# basic_schematic_pullup.net
KiCad netlist of a schematic drawn in EAGLE
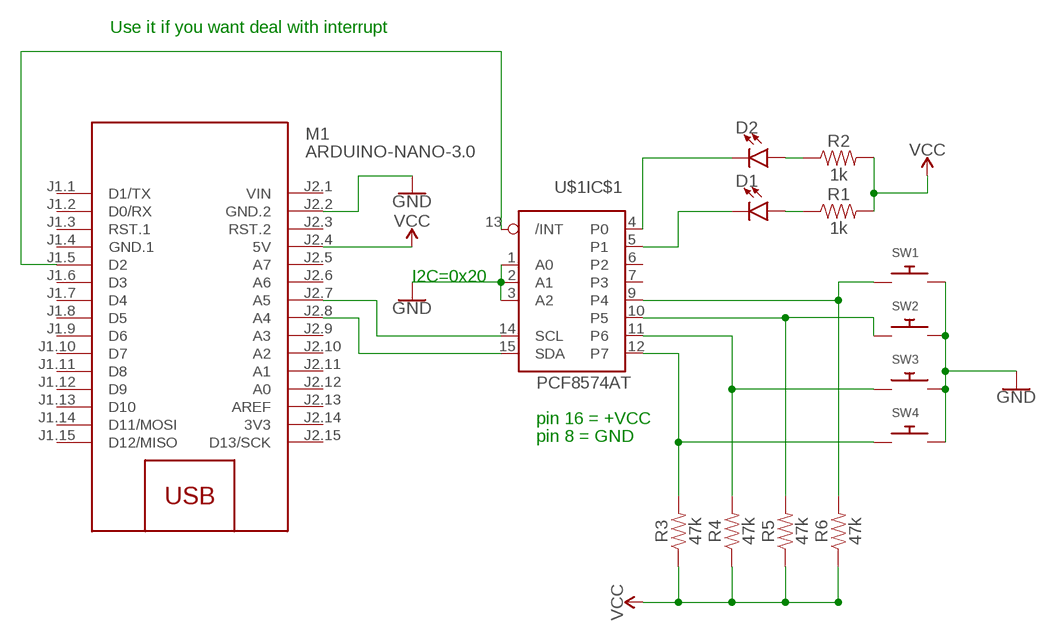
[diagram p0: schematic, sheet 1]

(export (version "E")
  (design (tool "Eeschema 10.0.6"))
  (components
    (comp (ref "D1")
      (value "LED3MM")
      (footprint "eagle-import:LED_3MM")
      (libsource (lib "eagle-import") (part "LED3MM"))
    )
    (comp (ref "D2")
      (value "LED3MM")
      (footprint "eagle-import:LED_3MM")
      (libsource (lib "eagle-import") (part "LED3MM"))
    )
    (comp (ref "M1")
      (value "ARDUINO-NANO-3.0")
      (footprint "eagle-import:ARDUINO-NANO-3.0")
      (libsource (lib "eagle-import") (part "ARDUINO-NANO-3.0"))
    )
    (comp (ref "R1")
      (value "1k")
      (footprint "eagle-import:0603")
      (libsource (lib "eagle-import") (part "1KOHM-0603-1/10W-1%"))
    )
    (comp (ref "R2")
      (value "1k")
      (footprint "eagle-import:0603")
      (libsource (lib "eagle-import") (part "1KOHM-0603-1/10W-1%"))
    )
    (comp (ref "R3")
      (value "47k")
      (footprint "eagle-import:0603")
      (libsource (lib "eagle-import") (part "47KOHM-0603-1/10W-1%"))
    )
    (comp (ref "R4")
      (value "47k")
      (footprint "eagle-import:0603")
      (libsource (lib "eagle-import") (part "47KOHM-0603-1/10W-1%"))
    )
    (comp (ref "R5")
      (value "47k")
      (footprint "eagle-import:0603")
      (libsource (lib "eagle-import") (part "47KOHM-0603-1/10W-1%"))
    )
    (comp (ref "R6")
      (value "47k")
      (footprint "eagle-import:0603")
      (libsource (lib "eagle-import") (part "47KOHM-0603-1/10W-1%"))
    )
    (comp (ref "SW1")
      (value "SWITCH_PUSHBUTTONC&K_KSS")
      (footprint "eagle-import:BTN_CK_KSS")
      (libsource (lib "eagle-import") (part "SWITCH_PUSHBUTTONC&K_KSS"))
    )
    (comp (ref "SW2")
      (value "SWITCH_PUSHBUTTONC&K_KSS")
      (footprint "eagle-import:BTN_CK_KSS")
      (libsource (lib "eagle-import") (part "SWITCH_PUSHBUTTONC&K_KSS"))
    )
    (comp (ref "SW3")
      (value "SWITCH_PUSHBUTTONC&K_KSS")
      (footprint "eagle-import:BTN_CK_KSS")
      (libsource (lib "eagle-import") (part "SWITCH_PUSHBUTTONC&K_KSS"))
    )
    (comp (ref "SW4")
      (value "SWITCH_PUSHBUTTONC&K_KSS")
      (footprint "eagle-import:BTN_CK_KSS")
      (libsource (lib "eagle-import") (part "SWITCH_PUSHBUTTONC&K_KSS"))
    )
    (comp (ref "U$1")
      (value "PCF8574AT")
      (footprint "eagle-import:SO16")
      (libsource (lib "eagle-import") (part "PCF8574AT"))
    )
  )
  (nets
    (net (code "1") (name "/3V3") (class "Default")
      (node (ref "M1") (pin "J2.14") (pinfunction "3V3_J2.14") (pintype "power_in"))
    )
    (net (code "2") (name "/GND.1") (class "Default")
      (node (ref "M1") (pin "J1.4") (pinfunction "GND.1_J1.4") (pintype "power_in"))
    )
    (net (code "3") (name "/VIN") (class "Default")
      (node (ref "M1") (pin "J2.1") (pinfunction "VIN_J2.1") (pintype "power_in"))
    )
    (net (code "4") (name "GND") (class "Default")
      (node (ref "M1") (pin "J2.2") (pinfunction "GND.2_J2.2") (pintype "power_in"))
      (node (ref "SW1") (pin "P$2") (pinfunction "P$2_P$2") (pintype "passive"))
      (node (ref "SW2") (pin "P$2") (pinfunction "P$2_P$2") (pintype "passive"))
      (node (ref "SW3") (pin "P$2") (pinfunction "P$2_P$2") (pintype "passive"))
      (node (ref "SW4") (pin "P$2") (pinfunction "P$2_P$2") (pintype "passive"))
      (node (ref "U$1") (pin "1") (pinfunction "A0_1") (pintype "input"))
      (node (ref "U$1") (pin "2") (pinfunction "A1_2") (pintype "input"))
      (node (ref "U$1") (pin "3") (pinfunction "A2_3") (pintype "input"))
    )
    (net (code "5") (name "Net-(D1-C)") (class "Default")
      (node (ref "D1") (pin "K") (pinfunction "C_K") (pintype "passive"))
      (node (ref "U$1") (pin "5") (pinfunction "P1_5") (pintype "bidirectional"))
    )
    (net (code "6") (name "Net-(D1-PadA)") (class "Default")
      (node (ref "D1") (pin "A") (pinfunction "A_A") (pintype "passive"))
      (node (ref "R1") (pin "1") (pinfunction "1_1") (pintype "passive"))
    )
    (net (code "7") (name "Net-(D2-C)") (class "Default")
      (node (ref "D2") (pin "K") (pinfunction "C_K") (pintype "passive"))
      (node (ref "U$1") (pin "4") (pinfunction "P0_4") (pintype "bidirectional"))
    )
    (net (code "8") (name "Net-(D2-PadA)") (class "Default")
      (node (ref "D2") (pin "A") (pinfunction "A_A") (pintype "passive"))
      (node (ref "R2") (pin "1") (pinfunction "1_1") (pintype "passive"))
    )
    (net (code "9") (name "Net-(M1-A4)") (class "Default")
      (node (ref "M1") (pin "J2.8") (pinfunction "A4_J2.8") (pintype "bidirectional"))
      (node (ref "U$1") (pin "15") (pinfunction "SDA_15") (pintype "bidirectional"))
    )
    (net (code "10") (name "Net-(M1-A5)") (class "Default")
      (node (ref "M1") (pin "J2.7") (pinfunction "A5_J2.7") (pintype "bidirectional"))
      (node (ref "U$1") (pin "14") (pinfunction "SCL_14") (pintype "input"))
    )
    (net (code "11") (name "Net-(M1-D2)") (class "Default")
      (node (ref "M1") (pin "J1.5") (pinfunction "D2_J1.5") (pintype "bidirectional"))
      (node (ref "U$1") (pin "13") (pinfunction "/INT_13") (pintype "output"))
    )
    (net (code "12") (name "Net-(U$1A-P4)") (class "Default")
      (node (ref "R6") (pin "2") (pinfunction "2_2") (pintype "passive"))
      (node (ref "SW1") (pin "P$1") (pinfunction "P$1_P$1") (pintype "passive"))
      (node (ref "U$1") (pin "9") (pinfunction "P4_9") (pintype "bidirectional"))
    )
    (net (code "13") (name "Net-(U$1A-P5)") (class "Default")
      (node (ref "R5") (pin "2") (pinfunction "2_2") (pintype "passive"))
      (node (ref "SW2") (pin "P$1") (pinfunction "P$1_P$1") (pintype "passive"))
      (node (ref "U$1") (pin "10") (pinfunction "P5_10") (pintype "bidirectional"))
    )
    (net (code "14") (name "Net-(U$1A-P6)") (class "Default")
      (node (ref "R4") (pin "2") (pinfunction "2_2") (pintype "passive"))
      (node (ref "SW3") (pin "P$1") (pinfunction "P$1_P$1") (pintype "passive"))
      (node (ref "U$1") (pin "11") (pinfunction "P6_11") (pintype "bidirectional"))
    )
    (net (code "15") (name "Net-(U$1A-P7)") (class "Default")
      (node (ref "R3") (pin "2") (pinfunction "2_2") (pintype "passive"))
      (node (ref "SW4") (pin "P$1") (pinfunction "P$1_P$1") (pintype "passive"))
      (node (ref "U$1") (pin "12") (pinfunction "P7_12") (pintype "bidirectional"))
    )
    (net (code "16") (name "VCC") (class "Default")
      (node (ref "M1") (pin "J2.4") (pinfunction "5V_J2.4") (pintype "power_in"))
      (node (ref "R1") (pin "2") (pinfunction "2_2") (pintype "passive"))
      (node (ref "R2") (pin "2") (pinfunction "2_2") (pintype "passive"))
      (node (ref "R3") (pin "1") (pinfunction "1_1") (pintype "passive"))
      (node (ref "R4") (pin "1") (pinfunction "1_1") (pintype "passive"))
      (node (ref "R5") (pin "1") (pinfunction "1_1") (pintype "passive"))
      (node (ref "R6") (pin "1") (pinfunction "1_1") (pintype "passive"))
    )
    (net (code "17") (name "unconnected-(M1-A0-PadJ2.12)") (class "Default")
      (node (ref "M1") (pin "J2.12") (pinfunction "A0_J2.12") (pintype "bidirectional"))
    )
    (net (code "18") (name "unconnected-(M1-A1-PadJ2.11)") (class "Default")
      (node (ref "M1") (pin "J2.11") (pinfunction "A1_J2.11") (pintype "bidirectional"))
    )
    (net (code "19") (name "unconnected-(M1-A2-PadJ2.10)") (class "Default")
      (node (ref "M1") (pin "J2.10") (pinfunction "A2_J2.10") (pintype "bidirectional"))
    )
    (net (code "20") (name "unconnected-(M1-A3-PadJ2.9)") (class "Default")
      (node (ref "M1") (pin "J2.9") (pinfunction "A3_J2.9") (pintype "bidirectional"))
    )
    (net (code "21") (name "unconnected-(M1-A6-PadJ2.6)") (class "Default")
      (node (ref "M1") (pin "J2.6") (pinfunction "A6_J2.6") (pintype "bidirectional"))
    )
    (net (code "22") (name "unconnected-(M1-A7-PadJ2.5)") (class "Default")
      (node (ref "M1") (pin "J2.5") (pinfunction "A7_J2.5") (pintype "bidirectional"))
    )
    (net (code "23") (name "unconnected-(M1-AREF-PadJ2.13)") (class "Default")
      (node (ref "M1") (pin "J2.13") (pinfunction "AREF_J2.13") (pintype "bidirectional"))
    )
    (net (code "24") (name "unconnected-(M1-D0{slash}RX-PadJ1.2)") (class "Default")
      (node (ref "M1") (pin "J1.2") (pinfunction "D0/RX_J1.2") (pintype "bidirectional"))
    )
    (net (code "25") (name "unconnected-(M1-D1{slash}TX-PadJ1.1)") (class "Default")
      (node (ref "M1") (pin "J1.1") (pinfunction "D1/TX_J1.1") (pintype "bidirectional"))
    )
    (net (code "26") (name "unconnected-(M1-D3-PadJ1.6)") (class "Default")
      (node (ref "M1") (pin "J1.6") (pinfunction "D3_J1.6") (pintype "bidirectional"))
    )
    (net (code "27") (name "unconnected-(M1-D4-PadJ1.7)") (class "Default")
      (node (ref "M1") (pin "J1.7") (pinfunction "D4_J1.7") (pintype "bidirectional"))
    )
    (net (code "28") (name "unconnected-(M1-D5-PadJ1.8)") (class "Default")
      (node (ref "M1") (pin "J1.8") (pinfunction "D5_J1.8") (pintype "bidirectional"))
    )
    (net (code "29") (name "unconnected-(M1-D6-PadJ1.9)") (class "Default")
      (node (ref "M1") (pin "J1.9") (pinfunction "D6_J1.9") (pintype "bidirectional"))
    )
    (net (code "30") (name "unconnected-(M1-D7-PadJ1.10)") (class "Default")
      (node (ref "M1") (pin "J1.10") (pinfunction "D7_J1.10") (pintype "bidirectional"))
    )
    (net (code "31") (name "unconnected-(M1-D8-PadJ1.11)") (class "Default")
      (node (ref "M1") (pin "J1.11") (pinfunction "D8_J1.11") (pintype "bidirectional"))
    )
    (net (code "32") (name "unconnected-(M1-D9-PadJ1.12)") (class "Default")
      (node (ref "M1") (pin "J1.12") (pinfunction "D9_J1.12") (pintype "bidirectional"))
    )
    (net (code "33") (name "unconnected-(M1-D10-PadJ1.13)") (class "Default")
      (node (ref "M1") (pin "J1.13") (pinfunction "D10_J1.13") (pintype "bidirectional"))
    )
    (net (code "34") (name "unconnected-(M1-D11{slash}MOSI-PadJ1.14)") (class "Default")
      (node (ref "M1") (pin "J1.14") (pinfunction "D11/MOSI_J1.14") (pintype "bidirectional"))
    )
    (net (code "35") (name "unconnected-(M1-D12{slash}MISO-PadJ1.15)") (class "Default")
      (node (ref "M1") (pin "J1.15") (pinfunction "D12/MISO_J1.15") (pintype "bidirectional"))
    )
    (net (code "36") (name "unconnected-(M1-D13{slash}SCK-PadJ2.15)") (class "Default")
      (node (ref "M1") (pin "J2.15") (pinfunction "D13/SCK_J2.15") (pintype "bidirectional"))
    )
    (net (code "37") (name "unconnected-(M1-RST.1-PadJ1.3)") (class "Default")
      (node (ref "M1") (pin "J1.3") (pinfunction "RST.1_J1.3") (pintype "bidirectional"))
    )
    (net (code "38") (name "unconnected-(M1-RST.2-PadJ2.3)") (class "Default")
      (node (ref "M1") (pin "J2.3") (pinfunction "RST.2_J2.3") (pintype "bidirectional"))
    )
    (net (code "39") (name "unconnected-(U$1A-P2-Pad6)") (class "Default")
      (node (ref "U$1") (pin "6") (pinfunction "P2_6") (pintype "bidirectional"))
    )
    (net (code "40") (name "unconnected-(U$1A-P3-Pad7)") (class "Default")
      (node (ref "U$1") (pin "7") (pinfunction "P3_7") (pintype "bidirectional"))
    )
  )
)
